# Controller.net
KiCad netlist of a schematic drawn in EAGLE
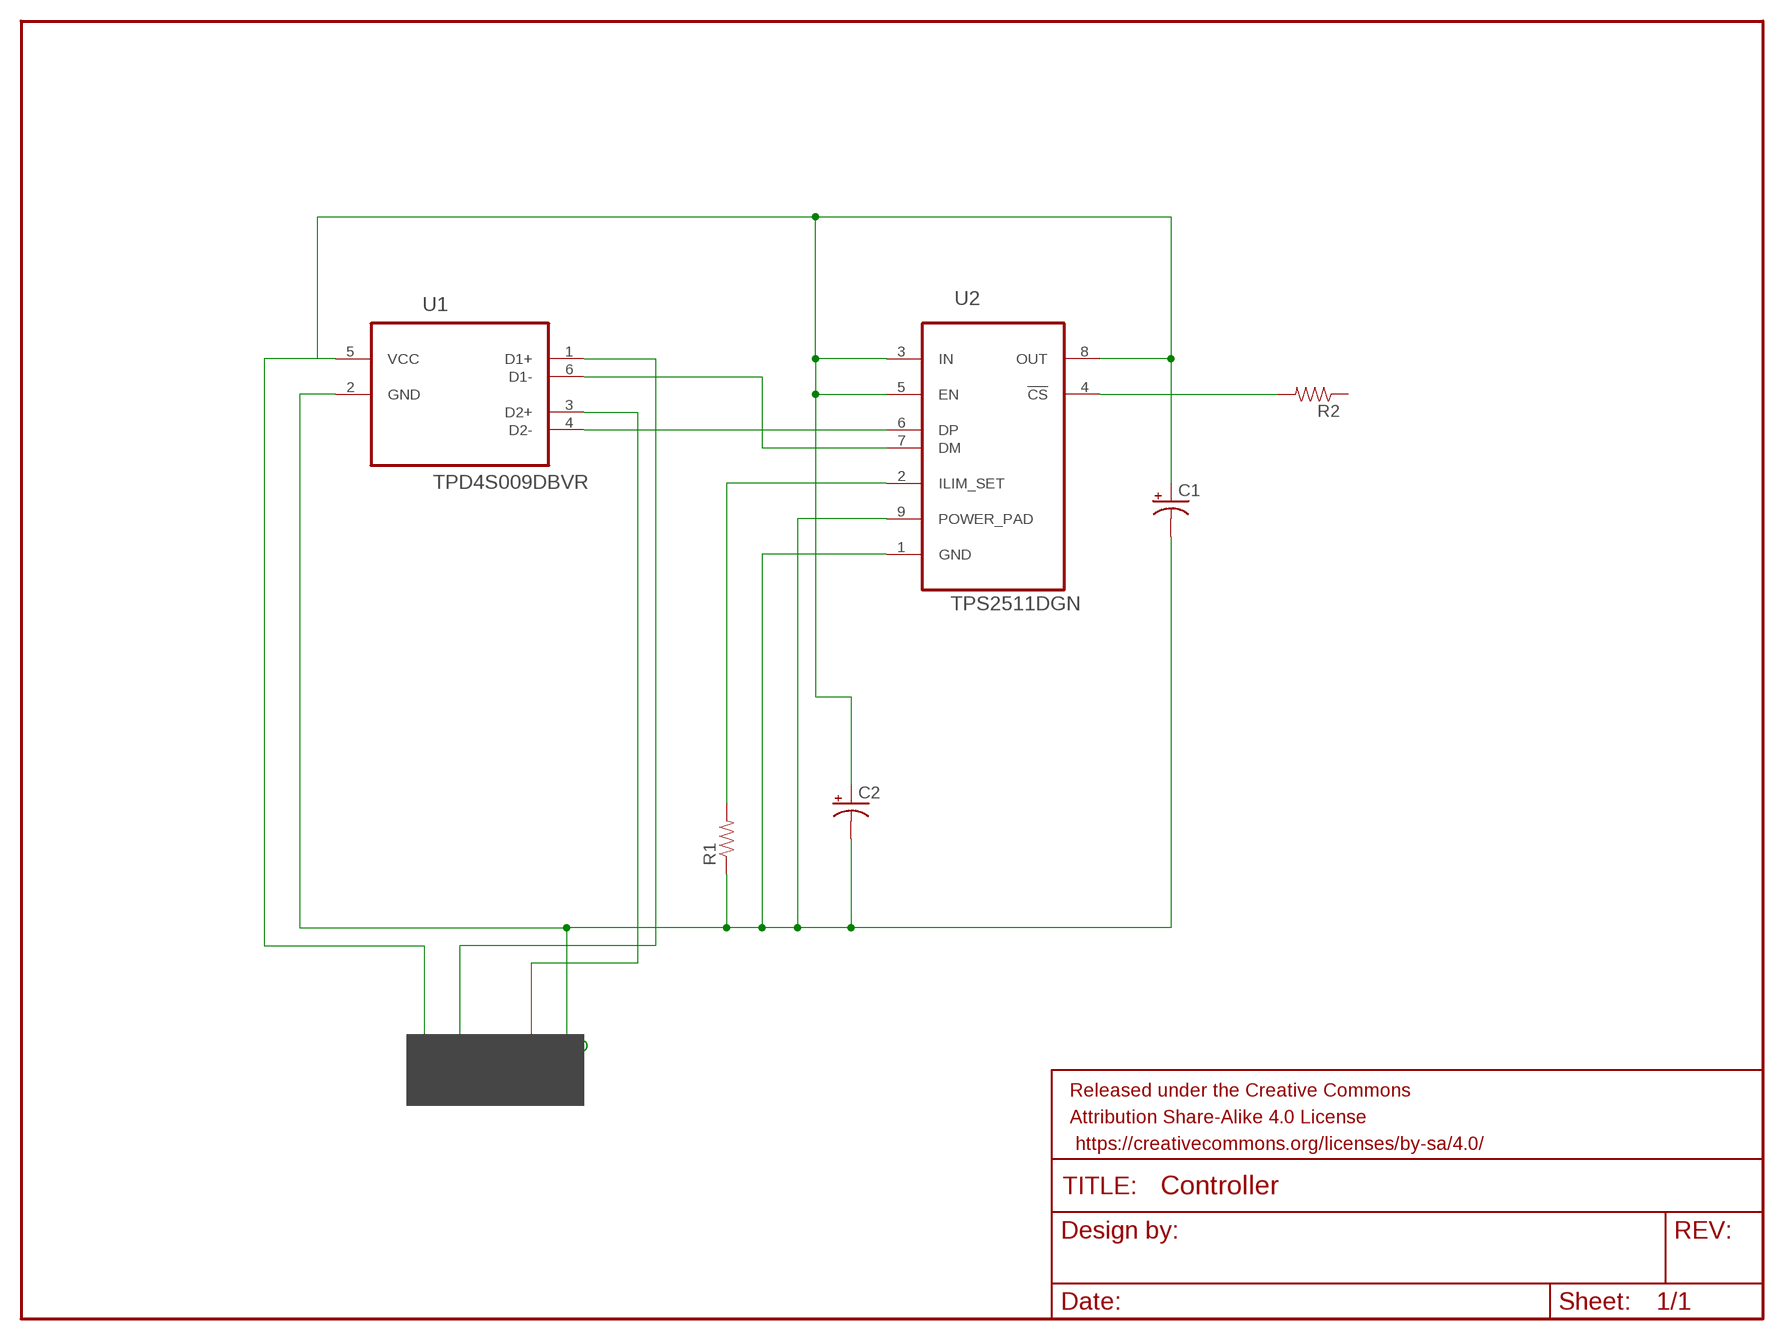
[diagram p0: schematic, sheet 1]

(export (version "E")
  (design (tool "Eeschema 10.0.6"))
  (components
    (comp (ref "C1")
      (value "CPOL-USE2-5")
      (footprint "eagle-import:E2-5")
      (libsource (lib "eagle-import") (part "CPOL-USE2-5"))
    )
    (comp (ref "C2")
      (value "CPOL-USE2-5")
      (footprint "eagle-import:E2-5")
      (libsource (lib "eagle-import") (part "CPOL-USE2-5"))
    )
    (comp (ref "FRAME1")
      (value "FRAME-LETTER")
      (footprint "eagle-import:CREATIVE_COMMONS")
      (libsource (lib "eagle-import") (part "FRAME-LETTER"))
    )
    (comp (ref "R1")
      (value "RESISTORKIT")
      (footprint "eagle-import:AXIAL-0.3-KIT")
      (libsource (lib "eagle-import") (part "RESISTORKIT"))
    )
    (comp (ref "R2")
      (value "RESISTORKIT")
      (footprint "eagle-import:AXIAL-0.3-KIT")
      (libsource (lib "eagle-import") (part "RESISTORKIT"))
    )
    (comp (ref "U1")
      (value "TPD4S009DBVR")
      (footprint "eagle-import:SOT95P280X145-6N")
      (libsource (lib "eagle-import") (part "TPD4S009DBVR"))
    )
    (comp (ref "U2")
      (value "TPS2511DGN")
      (footprint "eagle-import:SOP65P490X110-9N")
      (fields (field (name "MPN") "TPS2511DGN "))
      (libsource (lib "eagle-import") (part "TPS2511DGN"))
    )
  )
  (nets
    (net (code "1") (name "Net-(R1-1)") (class "Default")
      (node (ref "C1") (pin "-") (pinfunction "-_-") (pintype "passive"))
      (node (ref "C2") (pin "-") (pinfunction "-_-") (pintype "passive"))
      (node (ref "R1") (pin "P$1") (pinfunction "1_P$1") (pintype "passive"))
      (node (ref "U1") (pin "2") (pinfunction "GND_2") (pintype "passive"))
      (node (ref "U2") (pin "1") (pinfunction "GND_1") (pintype "passive"))
      (node (ref "U2") (pin "9") (pinfunction "POWER_PAD_9") (pintype "passive"))
    )
    (net (code "2") (name "Net-(R1-2)") (class "Default")
      (node (ref "R1") (pin "P$2") (pinfunction "2_P$2") (pintype "passive"))
      (node (ref "U2") (pin "2") (pinfunction "ILIM_SET_2") (pintype "input"))
    )
    (net (code "3") (name "Net-(R2-2)") (class "Default")
      (node (ref "R2") (pin "P$2") (pinfunction "2_P$2") (pintype "passive"))
      (node (ref "U2") (pin "4") (pinfunction "~{CS}_4") (pintype "output"))
    )
    (net (code "4") (name "Net-(U1-D1-)") (class "Default")
      (node (ref "U1") (pin "6") (pinfunction "D1-_6") (pintype "input"))
      (node (ref "U2") (pin "7") (pinfunction "DM_7") (pintype "bidirectional"))
    )
    (net (code "5") (name "Net-(U1-D2-)") (class "Default")
      (node (ref "U1") (pin "4") (pinfunction "D2-_4") (pintype "input"))
      (node (ref "U2") (pin "6") (pinfunction "DP_6") (pintype "bidirectional"))
    )
    (net (code "6") (name "Net-(U1-VCC)") (class "Default")
      (node (ref "C1") (pin "+") (pinfunction "+_+") (pintype "passive"))
      (node (ref "C2") (pin "+") (pinfunction "+_+") (pintype "passive"))
      (node (ref "U1") (pin "5") (pinfunction "VCC_5") (pintype "power_in"))
      (node (ref "U2") (pin "3") (pinfunction "IN_3") (pintype "power_in"))
      (node (ref "U2") (pin "5") (pinfunction "EN_5") (pintype "input"))
      (node (ref "U2") (pin "8") (pinfunction "OUT_8") (pintype "output"))
    )
    (net (code "7") (name "unconnected-(R2-1-PadP$1)") (class "Default")
      (node (ref "R2") (pin "P$1") (pinfunction "1_P$1") (pintype "passive"))
    )
    (net (code "8") (name "unconnected-(U1-D1+-Pad1)") (class "Default")
      (node (ref "U1") (pin "1") (pinfunction "D1+_1") (pintype "input"))
    )
    (net (code "9") (name "unconnected-(U1-D2+-Pad3)") (class "Default")
      (node (ref "U1") (pin "3") (pinfunction "D2+_3") (pintype "input"))
    )
  )
)
